# placa1.net
KiCad netlist of a schematic drawn in EAGLE
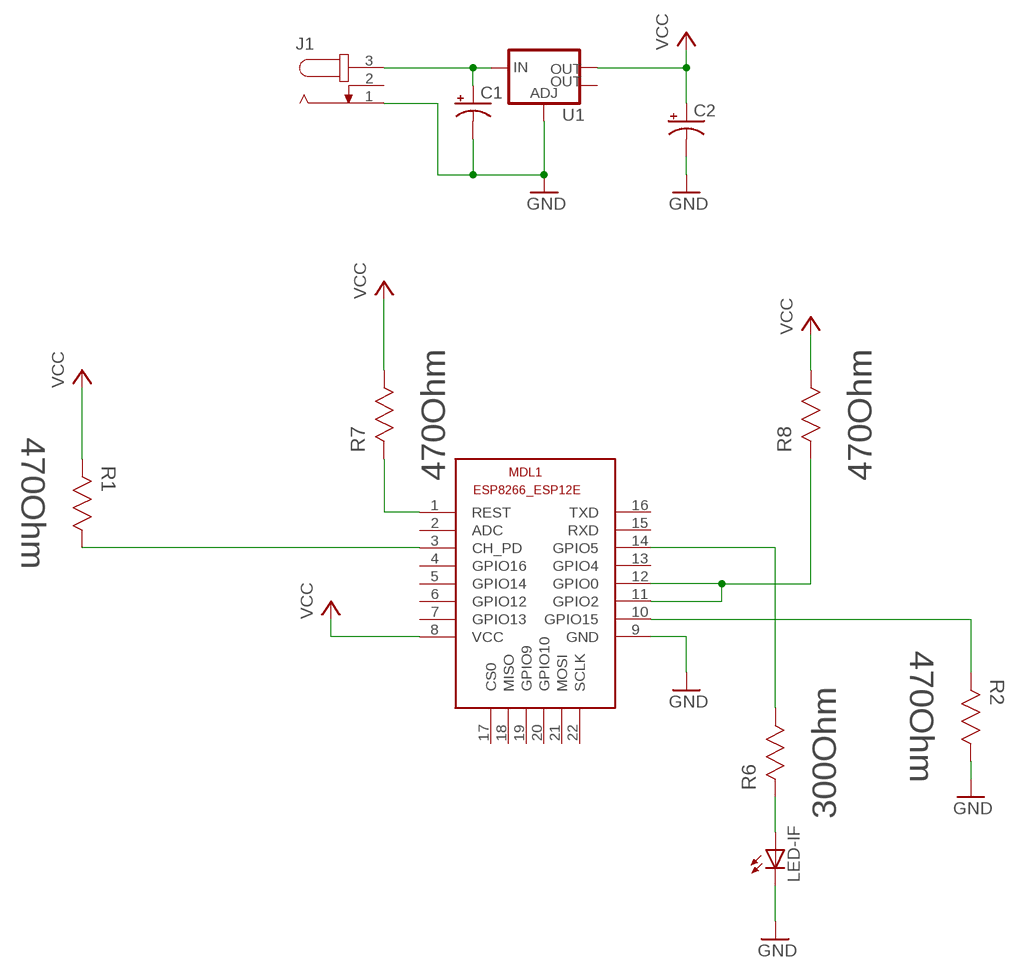
[diagram p0: schematic, sheet 1]

(export (version "E")
  (design (tool "Eeschema 10.0.6"))
  (components
    (comp (ref "C1")
      (value "CAP_POLC")
      (footprint "eagle-import:PANASONIC_C")
      (libsource (lib "eagle-import") (part "CAP_POLC"))
    )
    (comp (ref "C2")
      (value "CAP_POLC")
      (footprint "eagle-import:PANASONIC_C")
      (libsource (lib "eagle-import") (part "CAP_POLC"))
    )
    (comp (ref "J1")
      (value "JACK-PLUG0")
      (footprint "eagle-import:SPC4077")
      (libsource (lib "eagle-import") (part "JACK-PLUG0"))
    )
    (comp (ref "LED-IF")
      (value "LED5MM")
      (footprint "eagle-import:LED5MM")
      (libsource (lib "eagle-import") (part "LED5MM"))
    )
    (comp (ref "MDL1")
      (value "ESP8266-12EESP8266-ESP12E")
      (footprint "eagle-import:ESP8266-ESP12E")
      (libsource (lib "eagle-import") (part "ESP8266-12EESP8266-ESP12E"))
    )
    (comp (ref "R1")
      (value "470Ohm")
      (footprint "eagle-import:RESC2013X65N")
      (fields (field (name "MPN") "MCPWR05FTEW4700") (field (name "TOLERANCE") "± 1%"))
      (libsource (lib "eagle-import") (part "MCPWR05FTEW4700"))
    )
    (comp (ref "R2")
      (value "470Ohm")
      (footprint "eagle-import:RESC2013X65N")
      (fields (field (name "MPN") "MCPWR05FTEW4700") (field (name "TOLERANCE") "± 1%"))
      (libsource (lib "eagle-import") (part "MCPWR05FTEW4700"))
    )
    (comp (ref "R6")
      (value "300Ohm")
      (footprint "eagle-import:RESC2013X65N")
      (fields (field (name "MPN") "MCPWR05FTEW3000") (field (name "TOLERANCE") "± 1%"))
      (libsource (lib "eagle-import") (part "MCPWR05FTEW3000"))
    )
    (comp (ref "R7")
      (value "470Ohm")
      (footprint "eagle-import:RESC2013X65N")
      (fields (field (name "MPN") "MCPWR05FTEW4700") (field (name "TOLERANCE") "± 1%"))
      (libsource (lib "eagle-import") (part "MCPWR05FTEW4700"))
    )
    (comp (ref "R8")
      (value "470Ohm")
      (footprint "eagle-import:RESC2013X65N")
      (fields (field (name "MPN") "MCPWR05FTEW4700") (field (name "TOLERANCE") "± 1%"))
      (libsource (lib "eagle-import") (part "MCPWR05FTEW4700"))
    )
    (comp (ref "U1")
      (value "V_REG_LM1117SOT223")
      (footprint "eagle-import:SOT223")
      (libsource (lib "eagle-import") (part "V_REG_LM1117SOT223"))
    )
  )
  (nets
    (net (code "1") (name "GND") (class "Default")
      (node (ref "C1") (pin "-") (pinfunction "-_-") (pintype "passive"))
      (node (ref "C2") (pin "-") (pinfunction "-_-") (pintype "passive"))
      (node (ref "J1") (pin "1") (pinfunction "1_1") (pintype "passive"))
      (node (ref "LED-IF") (pin "K") (pinfunction "C_K") (pintype "passive"))
      (node (ref "MDL1") (pin "9") (pinfunction "GND_9") (pintype "bidirectional"))
      (node (ref "R2") (pin "1") (pinfunction "R1_1") (pintype "passive"))
      (node (ref "U1") (pin "1") (pinfunction "ADJ_1") (pintype "input"))
    )
    (net (code "2") (name "Net-(MDL1-CH_PD)") (class "Default")
      (node (ref "MDL1") (pin "3") (pinfunction "CH_PD_3") (pintype "bidirectional"))
      (node (ref "R1") (pin "1") (pinfunction "R1_1") (pintype "passive"))
    )
    (net (code "3") (name "Net-(MDL1-GPIO0)") (class "Default")
      (node (ref "MDL1") (pin "11") (pinfunction "GPIO2_11") (pintype "bidirectional"))
      (node (ref "MDL1") (pin "12") (pinfunction "GPIO0_12") (pintype "bidirectional"))
      (node (ref "R8") (pin "2") (pinfunction "R2_2") (pintype "passive"))
    )
    (net (code "4") (name "Net-(MDL1-GPIO5)") (class "Default")
      (node (ref "MDL1") (pin "14") (pinfunction "GPIO5_14") (pintype "bidirectional"))
      (node (ref "R6") (pin "1") (pinfunction "R1_1") (pintype "passive"))
    )
    (net (code "5") (name "Net-(MDL1-GPIO15)") (class "Default")
      (node (ref "MDL1") (pin "10") (pinfunction "GPIO15_10") (pintype "bidirectional"))
      (node (ref "R2") (pin "2") (pinfunction "R2_2") (pintype "passive"))
    )
    (net (code "6") (name "Net-(MDL1-REST)") (class "Default")
      (node (ref "MDL1") (pin "1") (pinfunction "REST_1") (pintype "bidirectional"))
      (node (ref "R7") (pin "2") (pinfunction "R2_2") (pintype "passive"))
    )
    (net (code "7") (name "Net-(R6-R2)") (class "Default")
      (node (ref "LED-IF") (pin "A") (pinfunction "A_A") (pintype "passive"))
      (node (ref "R6") (pin "2") (pinfunction "R2_2") (pintype "passive"))
    )
    (net (code "8") (name "Net-(U1-IN)") (class "Default")
      (node (ref "C1") (pin "+") (pinfunction "+_+") (pintype "passive"))
      (node (ref "J1") (pin "3") (pinfunction "3_3") (pintype "passive"))
      (node (ref "U1") (pin "3") (pinfunction "IN_3") (pintype "input"))
    )
    (net (code "9") (name "VCC") (class "Default")
      (node (ref "C2") (pin "+") (pinfunction "+_+") (pintype "passive"))
      (node (ref "MDL1") (pin "8") (pinfunction "VCC_8") (pintype "bidirectional"))
      (node (ref "R1") (pin "2") (pinfunction "R2_2") (pintype "passive"))
      (node (ref "R7") (pin "1") (pinfunction "R1_1") (pintype "passive"))
      (node (ref "R8") (pin "1") (pinfunction "R1_1") (pintype "passive"))
      (node (ref "U1") (pin "2") (pinfunction "OUT_2") (pintype "output"))
    )
    (net (code "10") (name "unconnected-(J1-Pad2)") (class "Default")
      (node (ref "J1") (pin "2") (pinfunction "2_2") (pintype "passive"))
    )
    (net (code "11") (name "unconnected-(MDL1-ADC-Pad2)") (class "Default")
      (node (ref "MDL1") (pin "2") (pinfunction "ADC_2") (pintype "bidirectional"))
    )
    (net (code "12") (name "unconnected-(MDL1-CS0-Pad17)") (class "Default")
      (node (ref "MDL1") (pin "17") (pinfunction "CS0_17") (pintype "bidirectional"))
    )
    (net (code "13") (name "unconnected-(MDL1-GPIO4-Pad13)") (class "Default")
      (node (ref "MDL1") (pin "13") (pinfunction "GPIO4_13") (pintype "bidirectional"))
    )
    (net (code "14") (name "unconnected-(MDL1-GPIO9-Pad19)") (class "Default")
      (node (ref "MDL1") (pin "19") (pinfunction "GPIO9_19") (pintype "bidirectional"))
    )
    (net (code "15") (name "unconnected-(MDL1-GPIO10-Pad20)") (class "Default")
      (node (ref "MDL1") (pin "20") (pinfunction "GPIO10_20") (pintype "bidirectional"))
    )
    (net (code "16") (name "unconnected-(MDL1-GPIO12-Pad6)") (class "Default")
      (node (ref "MDL1") (pin "6") (pinfunction "GPIO12_6") (pintype "bidirectional"))
    )
    (net (code "17") (name "unconnected-(MDL1-GPIO13-Pad7)") (class "Default")
      (node (ref "MDL1") (pin "7") (pinfunction "GPIO13_7") (pintype "bidirectional"))
    )
    (net (code "18") (name "unconnected-(MDL1-GPIO14-Pad5)") (class "Default")
      (node (ref "MDL1") (pin "5") (pinfunction "GPIO14_5") (pintype "bidirectional"))
    )
    (net (code "19") (name "unconnected-(MDL1-GPIO16-Pad4)") (class "Default")
      (node (ref "MDL1") (pin "4") (pinfunction "GPIO16_4") (pintype "bidirectional"))
    )
    (net (code "20") (name "unconnected-(MDL1-MISO-Pad18)") (class "Default")
      (node (ref "MDL1") (pin "18") (pinfunction "MISO_18") (pintype "bidirectional"))
    )
    (net (code "21") (name "unconnected-(MDL1-MOSI-Pad21)") (class "Default")
      (node (ref "MDL1") (pin "21") (pinfunction "MOSI_21") (pintype "bidirectional"))
    )
    (net (code "22") (name "unconnected-(MDL1-RXD-Pad15)") (class "Default")
      (node (ref "MDL1") (pin "15") (pinfunction "RXD_15") (pintype "bidirectional"))
    )
    (net (code "23") (name "unconnected-(MDL1-SCLK-Pad22)") (class "Default")
      (node (ref "MDL1") (pin "22") (pinfunction "SCLK_22") (pintype "bidirectional"))
    )
    (net (code "24") (name "unconnected-(MDL1-TXD-Pad16)") (class "Default")
      (node (ref "MDL1") (pin "16") (pinfunction "TXD_16") (pintype "bidirectional"))
    )
    (net (code "25") (name "unconnected-(U1-OUT-Pad4)") (class "Default")
      (node (ref "U1") (pin "4") (pinfunction "OUT_4") (pintype "output"))
    )
  )
)
